# main_board.net
KiCad netlist of a schematic drawn in EAGLE
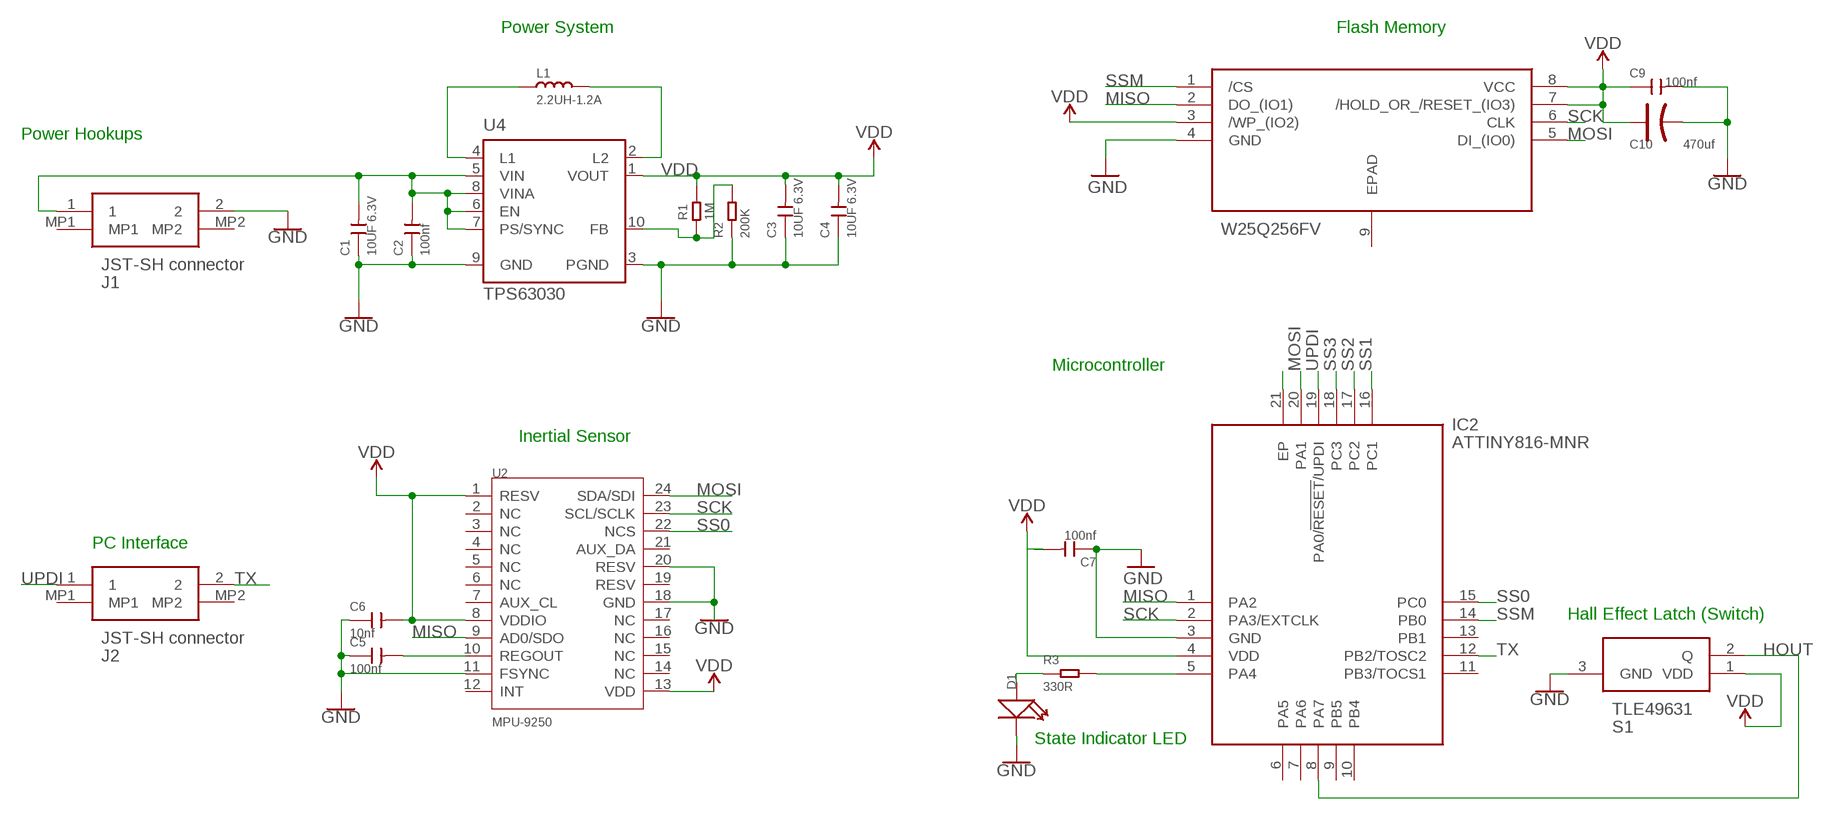
[diagram p0: schematic, sheet 1]

(export (version "E")
  (design (tool "Eeschema 10.0.6"))
  (components
    (comp (ref "C1")
      (value "10UF 6.3V")
      (footprint "eagle-import:C0603")
      (fields (field (name "MPN") "CC0603MRX5R5BB106"))
      (libsource (lib "eagle-import") (part "CERAMIC-10UF-6.3V-20%-X5R(0603)"))
    )
    (comp (ref "C2")
      (value "100nf")
      (footprint "eagle-import:C0603")
      (fields (field (name "MPN") "CC0603KRX7R9BB104"))
      (libsource (lib "eagle-import") (part "CERAMIC-100NF-50V-10%-X7R(0603)"))
    )
    (comp (ref "C3")
      (value "10UF 6.3V")
      (footprint "eagle-import:C0603")
      (fields (field (name "MPN") "CC0603MRX5R5BB106"))
      (libsource (lib "eagle-import") (part "CERAMIC-10UF-6.3V-20%-X5R(0603)"))
    )
    (comp (ref "C4")
      (value "10UF 6.3V")
      (footprint "eagle-import:C0603")
      (fields (field (name "MPN") "CC0603MRX5R5BB106"))
      (libsource (lib "eagle-import") (part "CERAMIC-10UF-6.3V-20%-X5R(0603)"))
    )
    (comp (ref "C5")
      (value "100nf")
      (footprint "eagle-import:C0402")
      (fields (field (name "MPN") "CC0402KRX7R8BB104"))
      (libsource (lib "eagle-import") (part "CERAMIC-100NF-25V-10%-X7R(0402)"))
    )
    (comp (ref "C6")
      (value "10nf")
      (footprint "eagle-import:C0402")
      (fields (field (name "MPN") "CC0402KRX7R9BB103"))
      (libsource (lib "eagle-import") (part "CERAMIC-10NF-50V-10%-X7R(0402)"))
    )
    (comp (ref "C7")
      (value "100nf")
      (footprint "eagle-import:C0603")
      (fields (field (name "MPN") "CC0603KRX7R9BB104"))
      (libsource (lib "eagle-import") (part "CERAMIC-100NF-50V-10%-X7R(0603)"))
    )
    (comp (ref "C9")
      (value "100nf")
      (footprint "eagle-import:C0603")
      (fields (field (name "MPN") "CC0603KRX7R9BB104"))
      (libsource (lib "eagle-import") (part "CERAMIC-100NF-50V-10%-X7R(0603)"))
    )
    (comp (ref "C10")
      (value "470uf")
      (footprint "eagle-import:AVX-D")
      (fields (field (name "MPN") "TAJD477*006#NJ"))
      (libsource (lib "eagle-import") (part "TANTALUM-SMD-470UF-6.3V(AVX-D)"))
    )
    (comp (ref "D1")
      (value "YELLOW-0603")
      (footprint "eagle-import:LED-0603")
      (fields (field (name "MPN") "19-217-Y5C-AM1N1VY-3T"))
      (libsource (lib "eagle-import") (part "SMD-LED-CLEAR-YELLOW(0603)"))
    )
    (comp (ref "IC1")
      (value "W25Q256FV")
      (footprint "eagle-import:SON127P800X600X80-9N")
      (fields (field (name "MANUFACTURER_PART_NUMBER") "W25Q256FVEIQ"))
      (libsource (lib "eagle-import") (part "W25Q256FVEIQ"))
    )
    (comp (ref "IC2")
      (value "ATTINY816-MNR")
      (footprint "eagle-import:QFN40P300X300X90-21N")
      (fields (field (name "MOUSER_PART_NUMBER") "579-ATTINY816-MNR"))
      (libsource (lib "eagle-import") (part "ATTINY816-MNR"))
    )
    (comp (ref "J1")
      (value "JST-SH connector")
      (footprint "eagle-import:BM02BSRSSTBLFSN")
      (fields (field (name "MANUFACTURER_PART_NUMBER") "BM02B-SRSS-TB(LF)(SN)"))
      (libsource (lib "eagle-import") (part "BM02B-SRSS-TB(LF)(SN)"))
    )
    (comp (ref "J2")
      (value "JST-SH connector")
      (footprint "eagle-import:BM02BSRSSTBLFSN")
      (fields (field (name "MANUFACTURER_PART_NUMBER") "BM02B-SRSS-TB(LF)(SN)"))
      (libsource (lib "eagle-import") (part "BM02B-SRSS-TB(LF)(SN)"))
    )
    (comp (ref "L1")
      (value "2.2UH-1.2A")
      (footprint "eagle-import:L0805")
      (fields (field (name "MPN") "LQM2MPN2R2MG0"))
      (libsource (lib "eagle-import") (part "SMD-INDUCTOR-2.2UH-20%-1.2A(0805)"))
    )
    (comp (ref "R1")
      (value "1M")
      (footprint "eagle-import:R0402")
      (fields (field (name "MPN") "RC0402JR-071ML"))
      (libsource (lib "eagle-import") (part "SMD-RES-1M-5%-1/16W(0402)"))
    )
    (comp (ref "R2")
      (value "200K")
      (footprint "eagle-import:R0603")
      (fields (field (name "MPN") "RC0603JR-07200KL"))
      (libsource (lib "eagle-import") (part "SMD-RES-200K-5%-1/10W(0603)"))
    )
    (comp (ref "R3")
      (value "330R")
      (footprint "eagle-import:R0402")
      (fields (field (name "MPN") "RC0402FR-07330RL"))
      (libsource (lib "eagle-import") (part "SMD-RES-330R-1%-1/16W(0402)"))
    )
    (comp (ref "S1")
      (value "TLE49631")
      (footprint "eagle-import:SOT95P240X110-3N")
      (fields (field (name "MANUFACTURER_PART_NUMBER") "TLE49631MXTSA1"))
      (libsource (lib "eagle-import") (part "TLE49631MXTSA1"))
    )
    (comp (ref "U2")
      (value "MPU-9250")
      (footprint "eagle-import:QFN24G-0.4-3X3MM")
      (libsource (lib "eagle-import") (part "MOTION/POSITION-MPU-9250(QFN24G)"))
    )
    (comp (ref "U4")
      (value "TPS63030")
      (footprint "eagle-import:DRC-S-PVSON-N10")
      (libsource (lib "eagle-import") (part "TPS63030DSKR"))
    )
  )
  (nets
    (net (code "1") (name "/HOUT") (class "Default")
      (node (ref "IC2") (pin "8") (pinfunction "PA7_8") (pintype "bidirectional"))
      (node (ref "S1") (pin "2") (pinfunction "Q_2") (pintype "output"))
    )
    (net (code "2") (name "/MISO") (class "Default")
      (node (ref "IC1") (pin "2") (pinfunction "DO_(IO1)_2") (pintype "bidirectional"))
      (node (ref "IC2") (pin "1") (pinfunction "PA2_1") (pintype "bidirectional"))
      (node (ref "U2") (pin "9") (pinfunction "AD0/SDO_9") (pintype "bidirectional"))
    )
    (net (code "3") (name "/MOSI") (class "Default")
      (node (ref "IC1") (pin "5") (pinfunction "DI_(IO0)_5") (pintype "bidirectional"))
      (node (ref "IC2") (pin "20") (pinfunction "PA1_20") (pintype "bidirectional"))
      (node (ref "U2") (pin "24") (pinfunction "SDA/SDI_24") (pintype "bidirectional"))
    )
    (net (code "4") (name "/SCK") (class "Default")
      (node (ref "IC1") (pin "6") (pinfunction "CLK_6") (pintype "bidirectional"))
      (node (ref "IC2") (pin "2") (pinfunction "PA3/EXTCLK_2") (pintype "bidirectional"))
      (node (ref "U2") (pin "23") (pinfunction "SCL/SCLK_23") (pintype "bidirectional"))
    )
    (net (code "5") (name "/SS0") (class "Default")
      (node (ref "IC2") (pin "15") (pinfunction "PC0_15") (pintype "bidirectional"))
      (node (ref "U2") (pin "22") (pinfunction "NCS_22") (pintype "bidirectional"))
    )
    (net (code "6") (name "/SS1") (class "Default")
      (node (ref "IC2") (pin "16") (pinfunction "PC1_16") (pintype "bidirectional"))
    )
    (net (code "7") (name "/SS2") (class "Default")
      (node (ref "IC2") (pin "17") (pinfunction "PC2_17") (pintype "bidirectional"))
    )
    (net (code "8") (name "/SS3") (class "Default")
      (node (ref "IC2") (pin "18") (pinfunction "PC3_18") (pintype "bidirectional"))
    )
    (net (code "9") (name "/SSM") (class "Default")
      (node (ref "IC1") (pin "1") (pinfunction "/CS_1") (pintype "bidirectional"))
      (node (ref "IC2") (pin "14") (pinfunction "PB0_14") (pintype "bidirectional"))
    )
    (net (code "10") (name "/TX") (class "Default")
      (node (ref "IC2") (pin "12") (pinfunction "PB2/TOSC2_12") (pintype "bidirectional"))
      (node (ref "J2") (pin "2") (pinfunction "2_2") (pintype "bidirectional"))
    )
    (net (code "11") (name "/UPDI") (class "Default")
      (node (ref "IC2") (pin "19") (pinfunction "PA0/~{RESET}/UPDI_19") (pintype "bidirectional"))
      (node (ref "J2") (pin "1") (pinfunction "1_1") (pintype "bidirectional"))
    )
    (net (code "12") (name "GND") (class "Default")
      (node (ref "C1") (pin "1") (pinfunction "1_1") (pintype "passive"))
      (node (ref "C10") (pin "-") (pinfunction "-_-") (pintype "passive"))
      (node (ref "C2") (pin "1") (pinfunction "1_1") (pintype "passive"))
      (node (ref "C3") (pin "1") (pinfunction "1_1") (pintype "passive"))
      (node (ref "C4") (pin "1") (pinfunction "1_1") (pintype "passive"))
      (node (ref "C5") (pin "1") (pinfunction "1_1") (pintype "passive"))
      (node (ref "C6") (pin "1") (pinfunction "1_1") (pintype "passive"))
      (node (ref "C7") (pin "1") (pinfunction "1_1") (pintype "passive"))
      (node (ref "C9") (pin "2") (pinfunction "2_2") (pintype "passive"))
      (node (ref "D1") (pin "-") (pinfunction "-_-") (pintype "passive"))
      (node (ref "IC1") (pin "4") (pinfunction "GND_4") (pintype "bidirectional"))
      (node (ref "IC2") (pin "3") (pinfunction "GND_3") (pintype "power_in"))
      (node (ref "J1") (pin "2") (pinfunction "2_2") (pintype "bidirectional"))
      (node (ref "R2") (pin "1") (pinfunction "1_1") (pintype "passive"))
      (node (ref "S1") (pin "3") (pinfunction "GND_3") (pintype "power_in"))
      (node (ref "U2") (pin "11") (pinfunction "FSYNC_11") (pintype "bidirectional"))
      (node (ref "U2") (pin "18") (pinfunction "GND_18") (pintype "bidirectional"))
      (node (ref "U2") (pin "20") (pinfunction "RESV_20") (pintype "bidirectional"))
      (node (ref "U4") (pin "3") (pinfunction "PGND_3") (pintype "power_in"))
      (node (ref "U4") (pin "9") (pinfunction "GND_9") (pintype "power_in"))
    )
    (net (code "13") (name "Net-(D1-Pad+)") (class "Default")
      (node (ref "D1") (pin "+") (pinfunction "+_+") (pintype "passive"))
      (node (ref "R3") (pin "1") (pinfunction "1_1") (pintype "passive"))
    )
    (net (code "14") (name "Net-(IC2-PA4)") (class "Default")
      (node (ref "IC2") (pin "5") (pinfunction "PA4_5") (pintype "bidirectional"))
      (node (ref "R3") (pin "2") (pinfunction "2_2") (pintype "passive"))
    )
    (net (code "15") (name "Net-(U2-REGOUT)") (class "Default")
      (node (ref "C5") (pin "2") (pinfunction "2_2") (pintype "passive"))
      (node (ref "U2") (pin "10") (pinfunction "REGOUT_10") (pintype "bidirectional"))
    )
    (net (code "16") (name "Net-(U4-EN)") (class "Default")
      (node (ref "C1") (pin "2") (pinfunction "2_2") (pintype "passive"))
      (node (ref "C2") (pin "2") (pinfunction "2_2") (pintype "passive"))
      (node (ref "J1") (pin "1") (pinfunction "1_1") (pintype "bidirectional"))
      (node (ref "U4") (pin "5") (pinfunction "VIN_5") (pintype "input"))
      (node (ref "U4") (pin "6") (pinfunction "EN_6") (pintype "input"))
      (node (ref "U4") (pin "7") (pinfunction "PS/SYNC_7") (pintype "input"))
      (node (ref "U4") (pin "8") (pinfunction "VINA_8") (pintype "input"))
    )
    (net (code "17") (name "Net-(U4-FB)") (class "Default")
      (node (ref "R1") (pin "1") (pinfunction "1_1") (pintype "passive"))
      (node (ref "R2") (pin "2") (pinfunction "2_2") (pintype "passive"))
      (node (ref "U4") (pin "10") (pinfunction "FB_10") (pintype "input"))
    )
    (net (code "18") (name "Net-(U4-L1)") (class "Default")
      (node (ref "L1") (pin "1") (pinfunction "1_1") (pintype "passive"))
      (node (ref "U4") (pin "4") (pinfunction "L1_4") (pintype "passive"))
    )
    (net (code "19") (name "Net-(U4-L2)") (class "Default")
      (node (ref "L1") (pin "2") (pinfunction "2_2") (pintype "passive"))
      (node (ref "U4") (pin "2") (pinfunction "L2_2") (pintype "passive"))
    )
    (net (code "20") (name "VDD") (class "Default")
      (node (ref "C10") (pin "+") (pinfunction "+_+") (pintype "passive"))
      (node (ref "C3") (pin "2") (pinfunction "2_2") (pintype "passive"))
      (node (ref "C4") (pin "2") (pinfunction "2_2") (pintype "passive"))
      (node (ref "C6") (pin "2") (pinfunction "2_2") (pintype "passive"))
      (node (ref "C7") (pin "2") (pinfunction "2_2") (pintype "passive"))
      (node (ref "C9") (pin "1") (pinfunction "1_1") (pintype "passive"))
      (node (ref "IC1") (pin "3") (pinfunction "/WP_(IO2)_3") (pintype "bidirectional"))
      (node (ref "IC1") (pin "7") (pinfunction "/HOLD_OR_/RESET_(IO3)_7") (pintype "bidirectional"))
      (node (ref "IC1") (pin "8") (pinfunction "VCC_8") (pintype "bidirectional"))
      (node (ref "IC2") (pin "4") (pinfunction "VDD_4") (pintype "power_in"))
      (node (ref "R1") (pin "2") (pinfunction "2_2") (pintype "passive"))
      (node (ref "S1") (pin "1") (pinfunction "VDD_1") (pintype "power_in"))
      (node (ref "U2") (pin "1") (pinfunction "RESV_1") (pintype "bidirectional"))
      (node (ref "U2") (pin "13") (pinfunction "VDD_13") (pintype "bidirectional"))
      (node (ref "U2") (pin "8") (pinfunction "VDDIO_8") (pintype "bidirectional"))
      (node (ref "U4") (pin "1") (pinfunction "VOUT_1") (pintype "output"))
    )
    (net (code "21") (name "unconnected-(IC1-EPAD-Pad9)") (class "Default")
      (node (ref "IC1") (pin "9") (pinfunction "EPAD_9") (pintype "bidirectional"))
    )
    (net (code "22") (name "unconnected-(IC2-EP-Pad21)") (class "Default")
      (node (ref "IC2") (pin "21") (pinfunction "EP_21") (pintype "power_in"))
    )
    (net (code "23") (name "unconnected-(IC2-PA5-Pad6)") (class "Default")
      (node (ref "IC2") (pin "6") (pinfunction "PA5_6") (pintype "bidirectional"))
    )
    (net (code "24") (name "unconnected-(IC2-PA6-Pad7)") (class "Default")
      (node (ref "IC2") (pin "7") (pinfunction "PA6_7") (pintype "bidirectional"))
    )
    (net (code "25") (name "unconnected-(IC2-PB1-Pad13)") (class "Default")
      (node (ref "IC2") (pin "13") (pinfunction "PB1_13") (pintype "bidirectional"))
    )
    (net (code "26") (name "unconnected-(IC2-PB3{slash}TOCS1-Pad11)") (class "Default")
      (node (ref "IC2") (pin "11") (pinfunction "PB3/TOCS1_11") (pintype "bidirectional"))
    )
    (net (code "27") (name "unconnected-(IC2-PB4-Pad10)") (class "Default")
      (node (ref "IC2") (pin "10") (pinfunction "PB4_10") (pintype "bidirectional"))
    )
    (net (code "28") (name "unconnected-(IC2-PB5-Pad9)") (class "Default")
      (node (ref "IC2") (pin "9") (pinfunction "PB5_9") (pintype "bidirectional"))
    )
    (net (code "29") (name "unconnected-(J1-PadMP1)") (class "Default")
      (node (ref "J1") (pin "MP1") (pinfunction "MP1_MP1") (pintype "bidirectional"))
    )
    (net (code "30") (name "unconnected-(J1-PadMP2)") (class "Default")
      (node (ref "J1") (pin "MP2") (pinfunction "MP2_MP2") (pintype "bidirectional"))
    )
    (net (code "31") (name "unconnected-(J2-PadMP1)") (class "Default")
      (node (ref "J2") (pin "MP1") (pinfunction "MP1_MP1") (pintype "bidirectional"))
    )
    (net (code "32") (name "unconnected-(J2-PadMP2)") (class "Default")
      (node (ref "J2") (pin "MP2") (pinfunction "MP2_MP2") (pintype "bidirectional"))
    )
    (net (code "33") (name "unconnected-(U2-AUX_CL-Pad7)") (class "Default")
      (node (ref "U2") (pin "7") (pinfunction "AUX_CL_7") (pintype "bidirectional"))
    )
    (net (code "34") (name "unconnected-(U2-AUX_DA-Pad21)") (class "Default")
      (node (ref "U2") (pin "21") (pinfunction "AUX_DA_21") (pintype "bidirectional"))
    )
    (net (code "35") (name "unconnected-(U2-INT-Pad12)") (class "Default")
      (node (ref "U2") (pin "12") (pinfunction "INT_12") (pintype "bidirectional"))
    )
    (net (code "36") (name "unconnected-(U2-NC-Pad2)") (class "Default")
      (node (ref "U2") (pin "2") (pinfunction "NC_2") (pintype "bidirectional"))
    )
    (net (code "37") (name "unconnected-(U2-NC-Pad3)") (class "Default")
      (node (ref "U2") (pin "3") (pinfunction "NC_3") (pintype "bidirectional"))
    )
    (net (code "38") (name "unconnected-(U2-NC-Pad4)") (class "Default")
      (node (ref "U2") (pin "4") (pinfunction "NC_4") (pintype "bidirectional"))
    )
    (net (code "39") (name "unconnected-(U2-NC-Pad5)") (class "Default")
      (node (ref "U2") (pin "5") (pinfunction "NC_5") (pintype "bidirectional"))
    )
    (net (code "40") (name "unconnected-(U2-NC-Pad6)") (class "Default")
      (node (ref "U2") (pin "6") (pinfunction "NC_6") (pintype "bidirectional"))
    )
    (net (code "41") (name "unconnected-(U2-NC-Pad14)") (class "Default")
      (node (ref "U2") (pin "14") (pinfunction "NC_14") (pintype "bidirectional"))
    )
    (net (code "42") (name "unconnected-(U2-NC-Pad15)") (class "Default")
      (node (ref "U2") (pin "15") (pinfunction "NC_15") (pintype "bidirectional"))
    )
    (net (code "43") (name "unconnected-(U2-NC-Pad16)") (class "Default")
      (node (ref "U2") (pin "16") (pinfunction "NC_16") (pintype "bidirectional"))
    )
    (net (code "44") (name "unconnected-(U2-NC-Pad17)") (class "Default")
      (node (ref "U2") (pin "17") (pinfunction "NC_17") (pintype "bidirectional"))
    )
    (net (code "45") (name "unconnected-(U2-RESV-Pad19)") (class "Default")
      (node (ref "U2") (pin "19") (pinfunction "RESV_19") (pintype "bidirectional"))
    )
  )
)
